# trackduino_ublox.net
KiCad netlist of a schematic drawn in EAGLE
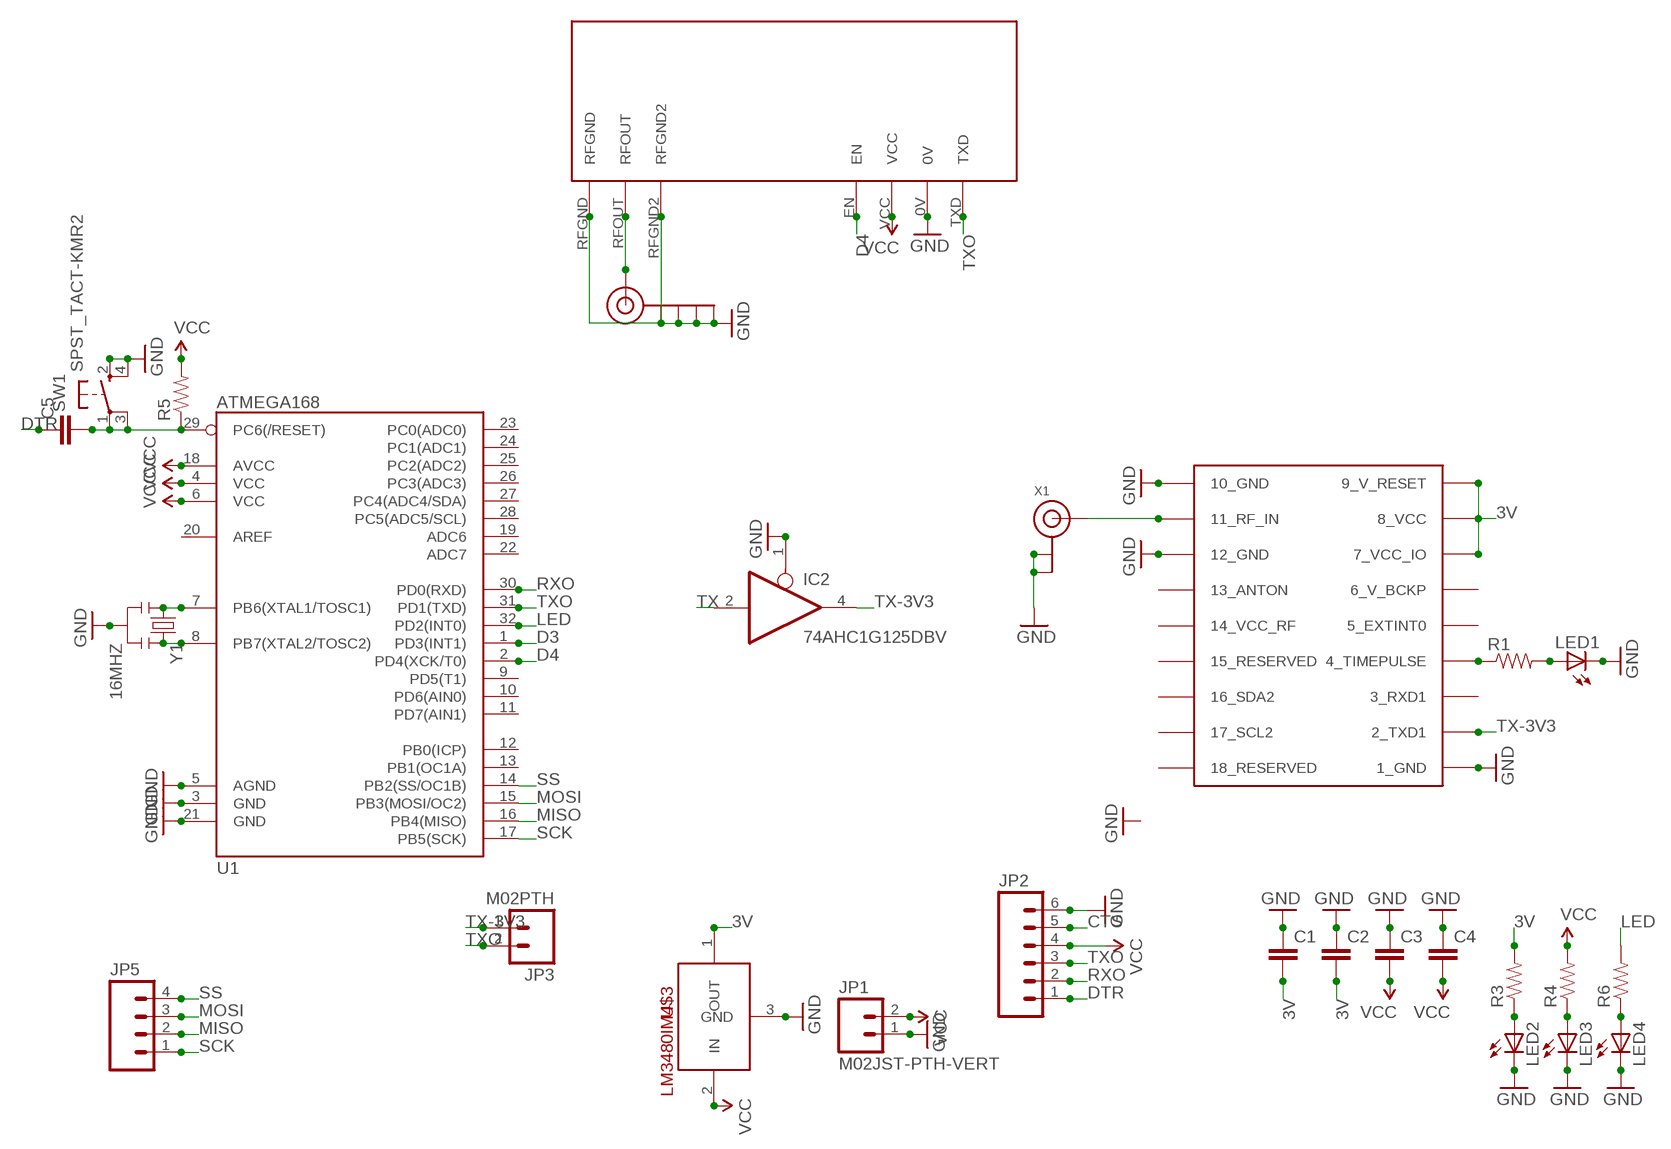
[diagram p0: schematic, sheet 1]

(export (version "E")
  (design (tool "Eeschema 10.0.6"))
  (components
    (comp (ref "C1")
      (value "CAP0805")
      (footprint "eagle-import:0805")
      (libsource (lib "eagle-import") (part "CAP0805"))
    )
    (comp (ref "C2")
      (value "CAP0805")
      (footprint "eagle-import:0805")
      (libsource (lib "eagle-import") (part "CAP0805"))
    )
    (comp (ref "C3")
      (value "CAP0805")
      (footprint "eagle-import:0805")
      (libsource (lib "eagle-import") (part "CAP0805"))
    )
    (comp (ref "C4")
      (value "CAP0805")
      (footprint "eagle-import:0805")
      (libsource (lib "eagle-import") (part "CAP0805"))
    )
    (comp (ref "C5")
      (value "CAP0805")
      (footprint "eagle-import:0805")
      (libsource (lib "eagle-import") (part "CAP0805"))
    )
    (comp (ref "IC2")
      (value "74AHC1G125DBV")
      (footprint "eagle-import:SOT23-5")
      (libsource (lib "eagle-import") (part "741G125DBVAHC"))
    )
    (comp (ref "J$1")
      (value "SMA_EDGE")
      (footprint "eagle-import:SMA-EDGE")
      (libsource (lib "eagle-import") (part "SMA_EDGE"))
    )
    (comp (ref "JP1")
      (value "M02JST-PTH-VERT")
      (footprint "eagle-import:JST-2-PTH-VERT")
      (libsource (lib "eagle-import") (part "M02JST-PTH-VERT"))
    )
    (comp (ref "JP2")
      (value "M06NO_SILK_FEMALE_PTH")
      (footprint "eagle-import:1X06_NO_SILK")
      (libsource (lib "eagle-import") (part "M06NO_SILK_FEMALE_PTH"))
    )
    (comp (ref "JP3")
      (value "M02PTH")
      (footprint "eagle-import:1X02")
      (libsource (lib "eagle-import") (part "M02PTH"))
    )
    (comp (ref "JP5")
      (value "M041X04_NO_SILK")
      (footprint "eagle-import:1X04_NO_SILK")
      (libsource (lib "eagle-import") (part "M041X04_NO_SILK"))
    )
    (comp (ref "LED1")
      (value "LEDCHIP-LED0805")
      (footprint "eagle-import:CHIP-LED0805")
      (libsource (lib "eagle-import") (part "LEDCHIP-LED0805"))
    )
    (comp (ref "LED2")
      (value "LEDCHIP-LED0805")
      (footprint "eagle-import:CHIP-LED0805")
      (libsource (lib "eagle-import") (part "LEDCHIP-LED0805"))
    )
    (comp (ref "LED3")
      (value "LEDCHIP-LED0805")
      (footprint "eagle-import:CHIP-LED0805")
      (libsource (lib "eagle-import") (part "LEDCHIP-LED0805"))
    )
    (comp (ref "LED4")
      (value "LEDCHIP-LED0805")
      (footprint "eagle-import:CHIP-LED0805")
      (libsource (lib "eagle-import") (part "LEDCHIP-LED0805"))
    )
    (comp (ref "R1")
      (value "RESISTOR0805-RES")
      (footprint "eagle-import:0805")
      (libsource (lib "eagle-import") (part "RESISTOR0805-RES"))
    )
    (comp (ref "R3")
      (value "RESISTOR0805-RES")
      (footprint "eagle-import:0805")
      (libsource (lib "eagle-import") (part "RESISTOR0805-RES"))
    )
    (comp (ref "R4")
      (value "RESISTOR0805-RES")
      (footprint "eagle-import:0805")
      (libsource (lib "eagle-import") (part "RESISTOR0805-RES"))
    )
    (comp (ref "R5")
      (value "RESISTOR0805-RES")
      (footprint "eagle-import:0805")
      (libsource (lib "eagle-import") (part "RESISTOR0805-RES"))
    )
    (comp (ref "R6")
      (value "RESISTOR0805-RES")
      (footprint "eagle-import:0805")
      (libsource (lib "eagle-import") (part "RESISTOR0805-RES"))
    )
    (comp (ref "SW1")
      (value "SPST_TACT-KMR2")
      (footprint "eagle-import:KMR2")
      (libsource (lib "eagle-import") (part "SPST_TACT-KMR2"))
    )
    (comp (ref "U$1")
      (value "UBLOX_MAX")
      (footprint "eagle-import:UBLOX_MAX")
      (libsource (lib "eagle-import") (part "UBLOX_MAX"))
    )
    (comp (ref "U$2")
      (value "RADIOMETRIX-HX1")
      (footprint "eagle-import:RADIOMETRIX-HX1")
      (libsource (lib "eagle-import") (part "RADIOMETRIX-HX1"))
    )
    (comp (ref "U$3")
      (value "LM3480IM4")
      (footprint "eagle-import:SOT23-3")
      (libsource (lib "eagle-import") (part "LM3480IM4"))
    )
    (comp (ref "U1")
      (value "ATMEGA168")
      (footprint "eagle-import:TQFP32-08")
      (libsource (lib "eagle-import") (part "ATMEGA168"))
    )
    (comp (ref "X1")
      (value "ANTENNA_U.FL")
      (footprint "eagle-import:U.FL")
      (libsource (lib "eagle-import") (part "ANTENNA_U.FL"))
    )
    (comp (ref "Y1")
      (value "16MHZ")
      (footprint "eagle-import:RESONATOR-SMD")
      (libsource (lib "eagle-import") (part "RESONATOR16MHZ"))
    )
  )
  (nets
    (net (code "1") (name "/3V") (class "Default")
      (node (ref "C1") (pin "2") (pinfunction "2_2") (pintype "passive"))
      (node (ref "C2") (pin "2") (pinfunction "2_2") (pintype "passive"))
      (node (ref "R3") (pin "2") (pinfunction "2_2") (pintype "passive"))
      (node (ref "U$1") (pin "7_VCC_IO") (pinfunction "7_VCC_IO_7_VCC_IO") (pintype "power_in"))
      (node (ref "U$1") (pin "8_VCC") (pinfunction "8_VCC_8_VCC") (pintype "power_in"))
      (node (ref "U$1") (pin "9_V_RESET") (pinfunction "9_V_RESET_9_V_RESET") (pintype "power_in"))
      (node (ref "U$3") (pin "1") (pinfunction "OUT_1") (pintype "bidirectional"))
    )
    (net (code "2") (name "/CTS") (class "Default")
      (node (ref "JP2") (pin "5") (pinfunction "5_5") (pintype "passive"))
    )
    (net (code "3") (name "/D3") (class "Default")
      (node (ref "U1") (pin "1") (pinfunction "PD3(INT1)_1") (pintype "bidirectional"))
    )
    (net (code "4") (name "/D4") (class "Default")
      (node (ref "U$2") (pin "EN") (pinfunction "EN_EN") (pintype "bidirectional"))
      (node (ref "U1") (pin "2") (pinfunction "PD4(XCK/T0)_2") (pintype "bidirectional"))
    )
    (net (code "5") (name "/DTR") (class "Default")
      (node (ref "C5") (pin "1") (pinfunction "1_1") (pintype "passive"))
      (node (ref "JP2") (pin "1") (pinfunction "1_1") (pintype "passive"))
    )
    (net (code "6") (name "/LED") (class "Default")
      (node (ref "R6") (pin "2") (pinfunction "2_2") (pintype "passive"))
      (node (ref "U1") (pin "32") (pinfunction "PD2(INT0)_32") (pintype "bidirectional"))
    )
    (net (code "7") (name "/MISO") (class "Default")
      (node (ref "JP5") (pin "2") (pinfunction "2_2") (pintype "passive"))
      (node (ref "U1") (pin "16") (pinfunction "PB4(MISO)_16") (pintype "bidirectional"))
    )
    (net (code "8") (name "/MOSI") (class "Default")
      (node (ref "JP5") (pin "3") (pinfunction "3_3") (pintype "passive"))
      (node (ref "U1") (pin "15") (pinfunction "PB3(MOSI/OC2)_15") (pintype "bidirectional"))
    )
    (net (code "9") (name "/RXO") (class "Default")
      (node (ref "JP2") (pin "2") (pinfunction "2_2") (pintype "passive"))
      (node (ref "U1") (pin "30") (pinfunction "PD0(RXD)_30") (pintype "bidirectional"))
    )
    (net (code "10") (name "/SCK") (class "Default")
      (node (ref "JP5") (pin "1") (pinfunction "1_1") (pintype "passive"))
      (node (ref "U1") (pin "17") (pinfunction "PB5(SCK)_17") (pintype "bidirectional"))
    )
    (net (code "11") (name "/SS") (class "Default")
      (node (ref "JP5") (pin "4") (pinfunction "4_4") (pintype "passive"))
      (node (ref "U1") (pin "14") (pinfunction "PB2(SS/OC1B)_14") (pintype "bidirectional"))
    )
    (net (code "12") (name "/TX") (class "Default")
      (node (ref "IC2") (pin "2") (pinfunction "I_2") (pintype "input"))
    )
    (net (code "13") (name "/TX-3V3") (class "Default")
      (node (ref "IC2") (pin "4") (pinfunction "O_4") (pintype "tri_state"))
      (node (ref "JP3") (pin "1") (pinfunction "1_1") (pintype "passive"))
      (node (ref "U$1") (pin "2_TXD1") (pinfunction "2_TXD1_2_TXD1") (pintype "bidirectional"))
    )
    (net (code "14") (name "/TXO") (class "Default")
      (node (ref "JP2") (pin "3") (pinfunction "3_3") (pintype "passive"))
      (node (ref "JP3") (pin "2") (pinfunction "2_2") (pintype "passive"))
      (node (ref "U$2") (pin "TXD") (pinfunction "TXD_TXD") (pintype "bidirectional"))
      (node (ref "U1") (pin "31") (pinfunction "PD1(TXD)_31") (pintype "bidirectional"))
    )
    (net (code "15") (name "GND") (class "Default")
      (node (ref "C1") (pin "1") (pinfunction "1_1") (pintype "passive"))
      (node (ref "C2") (pin "1") (pinfunction "1_1") (pintype "passive"))
      (node (ref "C3") (pin "1") (pinfunction "1_1") (pintype "passive"))
      (node (ref "C4") (pin "1") (pinfunction "1_1") (pintype "passive"))
      (node (ref "IC2") (pin "1") (pinfunction "OE_1") (pintype "input"))
      (node (ref "J$1") (pin "GND@0") (pinfunction "GND_GND@0") (pintype "bidirectional"))
      (node (ref "J$1") (pin "GND@1") (pinfunction "GND_GND@1") (pintype "bidirectional"))
      (node (ref "J$1") (pin "GND@2") (pinfunction "GND_GND@2") (pintype "bidirectional"))
      (node (ref "J$1") (pin "GND@3") (pinfunction "GND_GND@3") (pintype "bidirectional"))
      (node (ref "JP1") (pin "1") (pinfunction "1_1") (pintype "passive"))
      (node (ref "JP2") (pin "6") (pinfunction "6_6") (pintype "passive"))
      (node (ref "LED1") (pin "C") (pinfunction "C_C") (pintype "passive"))
      (node (ref "LED2") (pin "C") (pinfunction "C_C") (pintype "passive"))
      (node (ref "LED3") (pin "C") (pinfunction "C_C") (pintype "passive"))
      (node (ref "LED4") (pin "C") (pinfunction "C_C") (pintype "passive"))
      (node (ref "SW1") (pin "2") (pinfunction "S_2") (pintype "passive"))
      (node (ref "SW1") (pin "4") (pinfunction "S1_4") (pintype "passive"))
      (node (ref "U$1") (pin "10_GND") (pinfunction "10_GND_10_GND") (pintype "power_in"))
      (node (ref "U$1") (pin "12_GND") (pinfunction "12_GND_12_GND") (pintype "power_in"))
      (node (ref "U$1") (pin "1_GND") (pinfunction "1_GND_1_GND") (pintype "power_in"))
      (node (ref "U$2") (pin "0V") (pinfunction "0V_0V") (pintype "bidirectional"))
      (node (ref "U$2") (pin "RFGND") (pinfunction "RFGND_RFGND") (pintype "bidirectional"))
      (node (ref "U$2") (pin "RFGND2") (pinfunction "RFGND2_RFGND2") (pintype "bidirectional"))
      (node (ref "U$3") (pin "3") (pinfunction "GND_3") (pintype "bidirectional"))
      (node (ref "U1") (pin "21") (pinfunction "GND_21") (pintype "bidirectional"))
      (node (ref "U1") (pin "3") (pinfunction "GND_3") (pintype "bidirectional"))
      (node (ref "U1") (pin "5") (pinfunction "AGND_5") (pintype "bidirectional"))
      (node (ref "X1") (pin "1") (pinfunction "GND_1") (pintype "passive"))
      (node (ref "X1") (pin "2") (pinfunction "GND_2") (pintype "passive"))
      (node (ref "Y1") (pin "2") (pinfunction "2_2") (pintype "passive"))
    )
    (net (code "16") (name "Net-(J$1-SIGNAL)") (class "Default")
      (node (ref "J$1") (pin "SIG") (pinfunction "SIGNAL_SIG") (pintype "bidirectional"))
      (node (ref "U$2") (pin "RFOUT") (pinfunction "RFOUT_RFOUT") (pintype "bidirectional"))
    )
    (net (code "17") (name "Net-(LED1-PadA)") (class "Default")
      (node (ref "LED1") (pin "A") (pinfunction "A_A") (pintype "passive"))
      (node (ref "R1") (pin "2") (pinfunction "2_2") (pintype "passive"))
    )
    (net (code "18") (name "Net-(LED2-PadA)") (class "Default")
      (node (ref "LED2") (pin "A") (pinfunction "A_A") (pintype "passive"))
      (node (ref "R3") (pin "1") (pinfunction "1_1") (pintype "passive"))
    )
    (net (code "19") (name "Net-(LED3-PadA)") (class "Default")
      (node (ref "LED3") (pin "A") (pinfunction "A_A") (pintype "passive"))
      (node (ref "R4") (pin "1") (pinfunction "1_1") (pintype "passive"))
    )
    (net (code "20") (name "Net-(LED4-PadA)") (class "Default")
      (node (ref "LED4") (pin "A") (pinfunction "A_A") (pintype "passive"))
      (node (ref "R6") (pin "1") (pinfunction "1_1") (pintype "passive"))
    )
    (net (code "21") (name "Net-(R1-Pad1)") (class "Default")
      (node (ref "R1") (pin "1") (pinfunction "1_1") (pintype "passive"))
      (node (ref "U$1") (pin "4_TIMEPULSE") (pinfunction "4_TIMEPULSE_4_TIMEPULSE") (pintype "bidirectional"))
    )
    (net (code "22") (name "Net-(SW1-P)") (class "Default")
      (node (ref "C5") (pin "2") (pinfunction "2_2") (pintype "passive"))
      (node (ref "R5") (pin "1") (pinfunction "1_1") (pintype "passive"))
      (node (ref "SW1") (pin "1") (pinfunction "P_1") (pintype "passive"))
      (node (ref "SW1") (pin "3") (pinfunction "P1_3") (pintype "passive"))
      (node (ref "U1") (pin "29") (pinfunction "PC6(/RESET)_29") (pintype "bidirectional"))
    )
    (net (code "23") (name "Net-(U1-PB6(XTAL1{slash}TOSC1))") (class "Default")
      (node (ref "U1") (pin "7") (pinfunction "PB6(XTAL1/TOSC1)_7") (pintype "bidirectional"))
      (node (ref "Y1") (pin "1") (pinfunction "1_1") (pintype "passive"))
    )
    (net (code "24") (name "Net-(U1-PB7(XTAL2{slash}TOSC2))") (class "Default")
      (node (ref "U1") (pin "8") (pinfunction "PB7(XTAL2/TOSC2)_8") (pintype "bidirectional"))
      (node (ref "Y1") (pin "3") (pinfunction "3_3") (pintype "passive"))
    )
    (net (code "25") (name "Net-(X1-SIGNAL)") (class "Default")
      (node (ref "U$1") (pin "11_RF_IN") (pinfunction "11_RF_IN_11_RF_IN") (pintype "bidirectional"))
      (node (ref "X1") (pin "3") (pinfunction "SIGNAL_3") (pintype "passive"))
    )
    (net (code "26") (name "VCC") (class "Default")
      (node (ref "C3") (pin "2") (pinfunction "2_2") (pintype "passive"))
      (node (ref "C4") (pin "2") (pinfunction "2_2") (pintype "passive"))
      (node (ref "JP1") (pin "2") (pinfunction "2_2") (pintype "passive"))
      (node (ref "JP2") (pin "4") (pinfunction "4_4") (pintype "passive"))
      (node (ref "R4") (pin "2") (pinfunction "2_2") (pintype "passive"))
      (node (ref "R5") (pin "2") (pinfunction "2_2") (pintype "passive"))
      (node (ref "U$2") (pin "VCC") (pinfunction "VCC_VCC") (pintype "bidirectional"))
      (node (ref "U$3") (pin "2") (pinfunction "IN_2") (pintype "bidirectional"))
      (node (ref "U1") (pin "18") (pinfunction "AVCC_18") (pintype "bidirectional"))
      (node (ref "U1") (pin "4") (pinfunction "VCC_4") (pintype "bidirectional"))
      (node (ref "U1") (pin "6") (pinfunction "VCC_6") (pintype "bidirectional"))
    )
    (net (code "27") (name "unconnected-(U$1-Pad3_RXD1)") (class "Default")
      (node (ref "U$1") (pin "3_RXD1") (pinfunction "3_RXD1_3_RXD1") (pintype "bidirectional"))
    )
    (net (code "28") (name "unconnected-(U$1-Pad5_EXTINT0)") (class "Default")
      (node (ref "U$1") (pin "5_EXTINT0") (pinfunction "5_EXTINT0_5_EXTINT0") (pintype "bidirectional"))
    )
    (net (code "29") (name "unconnected-(U$1-Pad6_V_BCKP)") (class "Default")
      (node (ref "U$1") (pin "6_V_BCKP") (pinfunction "6_V_BCKP_6_V_BCKP") (pintype "bidirectional"))
    )
    (net (code "30") (name "unconnected-(U$1-Pad13_ANTON)") (class "Default")
      (node (ref "U$1") (pin "13_ANTON") (pinfunction "13_ANTON_13_ANTON") (pintype "bidirectional"))
    )
    (net (code "31") (name "unconnected-(U$1-Pad14_VCC_RF)") (class "Default")
      (node (ref "U$1") (pin "14_VCC_RF") (pinfunction "14_VCC_RF_14_VCC_RF") (pintype "bidirectional"))
    )
    (net (code "32") (name "unconnected-(U$1-Pad15_RESERVED)") (class "Default")
      (node (ref "U$1") (pin "15_RESERVED") (pinfunction "15_RESERVED_15_RESERVED") (pintype "bidirectional"))
    )
    (net (code "33") (name "unconnected-(U$1-Pad16_SDA2)") (class "Default")
      (node (ref "U$1") (pin "16_SDA2") (pinfunction "16_SDA2_16_SDA2") (pintype "bidirectional"))
    )
    (net (code "34") (name "unconnected-(U$1-Pad17_SCL2)") (class "Default")
      (node (ref "U$1") (pin "17_SCL2") (pinfunction "17_SCL2_17_SCL2") (pintype "bidirectional"))
    )
    (net (code "35") (name "unconnected-(U$1-Pad18_RESERVED)") (class "Default")
      (node (ref "U$1") (pin "18_RESERVED") (pinfunction "18_RESERVED_18_RESERVED") (pintype "bidirectional"))
    )
    (net (code "36") (name "unconnected-(U1-ADC6-Pad19)") (class "Default")
      (node (ref "U1") (pin "19") (pinfunction "ADC6_19") (pintype "bidirectional"))
    )
    (net (code "37") (name "unconnected-(U1-ADC7-Pad22)") (class "Default")
      (node (ref "U1") (pin "22") (pinfunction "ADC7_22") (pintype "bidirectional"))
    )
    (net (code "38") (name "unconnected-(U1-AREF-Pad20)") (class "Default")
      (node (ref "U1") (pin "20") (pinfunction "AREF_20") (pintype "bidirectional"))
    )
    (net (code "39") (name "unconnected-(U1-PB0(ICP)-Pad12)") (class "Default")
      (node (ref "U1") (pin "12") (pinfunction "PB0(ICP)_12") (pintype "bidirectional"))
    )
    (net (code "40") (name "unconnected-(U1-PB1(OC1A)-Pad13)") (class "Default")
      (node (ref "U1") (pin "13") (pinfunction "PB1(OC1A)_13") (pintype "bidirectional"))
    )
    (net (code "41") (name "unconnected-(U1-PC0(ADC0)-Pad23)") (class "Default")
      (node (ref "U1") (pin "23") (pinfunction "PC0(ADC0)_23") (pintype "bidirectional"))
    )
    (net (code "42") (name "unconnected-(U1-PC1(ADC1)-Pad24)") (class "Default")
      (node (ref "U1") (pin "24") (pinfunction "PC1(ADC1)_24") (pintype "bidirectional"))
    )
    (net (code "43") (name "unconnected-(U1-PC2(ADC2)-Pad25)") (class "Default")
      (node (ref "U1") (pin "25") (pinfunction "PC2(ADC2)_25") (pintype "bidirectional"))
    )
    (net (code "44") (name "unconnected-(U1-PC3(ADC3)-Pad26)") (class "Default")
      (node (ref "U1") (pin "26") (pinfunction "PC3(ADC3)_26") (pintype "bidirectional"))
    )
    (net (code "45") (name "unconnected-(U1-PC4(ADC4{slash}SDA)-Pad27)") (class "Default")
      (node (ref "U1") (pin "27") (pinfunction "PC4(ADC4/SDA)_27") (pintype "bidirectional"))
    )
    (net (code "46") (name "unconnected-(U1-PC5(ADC5{slash}SCL)-Pad28)") (class "Default")
      (node (ref "U1") (pin "28") (pinfunction "PC5(ADC5/SCL)_28") (pintype "bidirectional"))
    )
    (net (code "47") (name "unconnected-(U1-PD5(T1)-Pad9)") (class "Default")
      (node (ref "U1") (pin "9") (pinfunction "PD5(T1)_9") (pintype "bidirectional"))
    )
    (net (code "48") (name "unconnected-(U1-PD6(AIN0)-Pad10)") (class "Default")
      (node (ref "U1") (pin "10") (pinfunction "PD6(AIN0)_10") (pintype "bidirectional"))
    )
    (net (code "49") (name "unconnected-(U1-PD7(AIN1)-Pad11)") (class "Default")
      (node (ref "U1") (pin "11") (pinfunction "PD7(AIN1)_11") (pintype "bidirectional"))
    )
  )
)
